# arduino_isp_shield.net
KiCad netlist of a schematic drawn in EAGLE
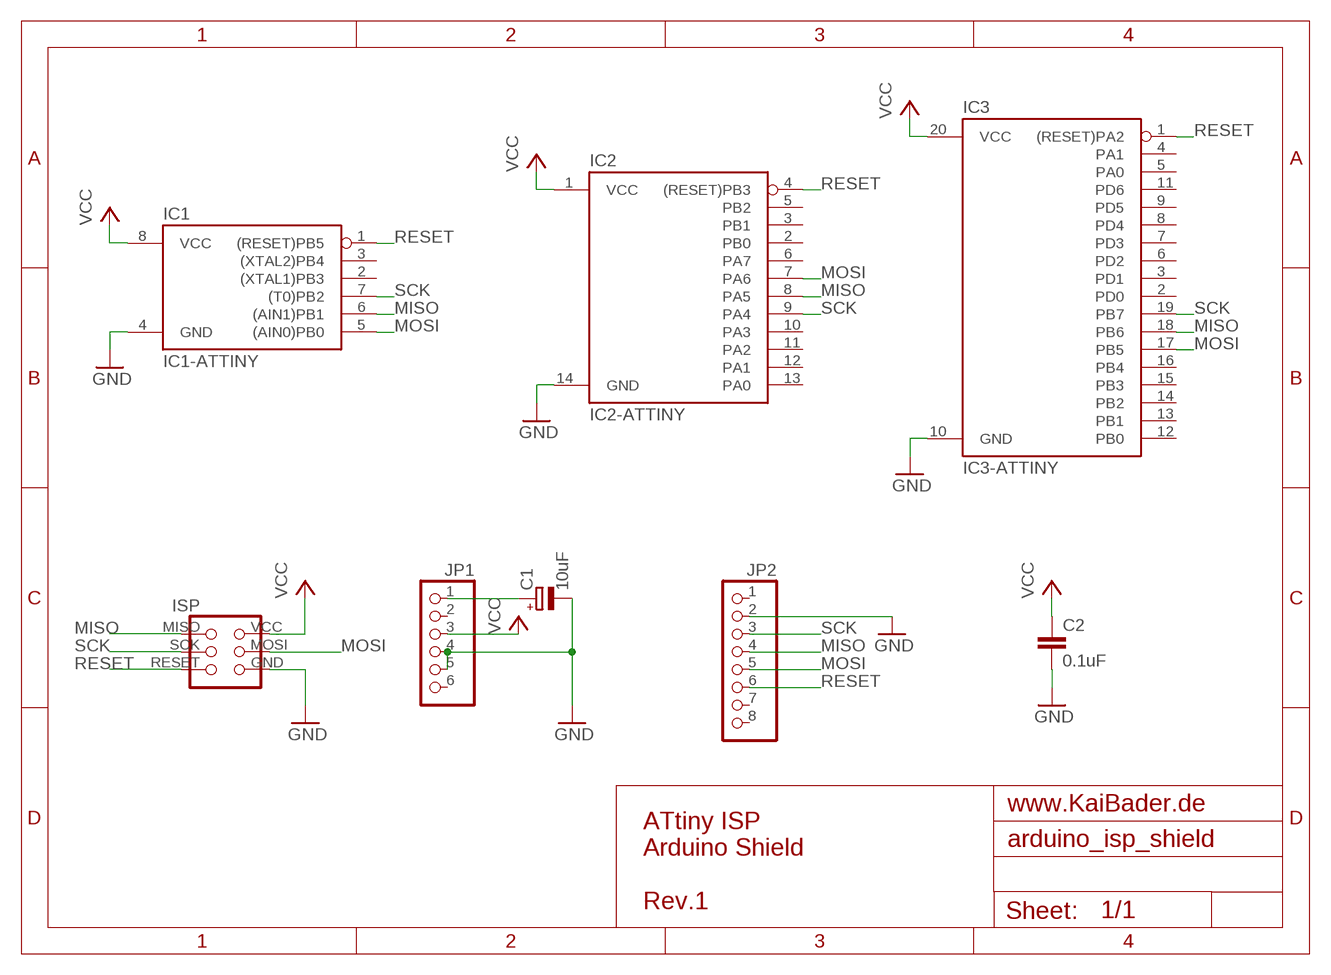
[diagram p0: schematic, sheet 1]

(export (version "E")
  (design (tool "Eeschema 10.0.6"))
  (components
    (comp (ref "C1")
      (value "10uF")
      (footprint "eagle-import:E1,8-4")
      (libsource (lib "eagle-import") (part "CPOL-EUE1.8-4"))
    )
    (comp (ref "C2")
      (value "0.1uF")
      (footprint "eagle-import:C050-025X075")
      (libsource (lib "eagle-import") (part "C-EU050-025X075"))
    )
    (comp (ref "IC1")
      (value "IC1-ATTINY")
      (footprint "eagle-import:DIL08")
      (libsource (lib "eagle-import") (part "TINY85P"))
    )
    (comp (ref "IC2")
      (value "IC2-ATTINY")
      (footprint "eagle-import:DIL14")
      (libsource (lib "eagle-import") (part "TINY84"))
    )
    (comp (ref "IC3")
      (value "IC3-ATTINY")
      (footprint "eagle-import:DIL20")
      (libsource (lib "eagle-import") (part "TINY2313"))
    )
    (comp (ref "ISP")
      (value "AVR-ISP")
      (footprint "eagle-import:AVR-ISP")
      (libsource (lib "eagle-import") (part "AVR-ISP"))
    )
    (comp (ref "JP1")
      (value "PINHD-1X6")
      (footprint "eagle-import:1X06")
      (libsource (lib "eagle-import") (part "PINHD-1X6"))
    )
    (comp (ref "JP2")
      (value "PINHD-1X8")
      (footprint "eagle-import:1X08")
      (libsource (lib "eagle-import") (part "PINHD-1X8"))
    )
  )
  (nets
    (net (code "1") (name "/MISO") (class "Default")
      (node (ref "IC1") (pin "6") (pinfunction "(AIN1)PB1_6") (pintype "bidirectional"))
      (node (ref "IC2") (pin "8") (pinfunction "PA5_8") (pintype "bidirectional"))
      (node (ref "IC3") (pin "18") (pinfunction "PB6_18") (pintype "bidirectional"))
      (node (ref "ISP") (pin "MISO") (pinfunction "MISO_MISO") (pintype "bidirectional"))
      (node (ref "JP2") (pin "4") (pinfunction "4_4") (pintype "passive"))
    )
    (net (code "2") (name "/MOSI") (class "Default")
      (node (ref "IC1") (pin "5") (pinfunction "(AIN0)PB0_5") (pintype "bidirectional"))
      (node (ref "IC2") (pin "7") (pinfunction "PA6_7") (pintype "bidirectional"))
      (node (ref "IC3") (pin "17") (pinfunction "PB5_17") (pintype "bidirectional"))
      (node (ref "ISP") (pin "MOSI") (pinfunction "MOSI_MOSI") (pintype "bidirectional"))
      (node (ref "JP2") (pin "5") (pinfunction "5_5") (pintype "passive"))
    )
    (net (code "3") (name "/RESET") (class "Default")
      (node (ref "IC1") (pin "1") (pinfunction "(RESET)PB5_1") (pintype "bidirectional"))
      (node (ref "IC2") (pin "4") (pinfunction "(RESET)PB3_4") (pintype "bidirectional"))
      (node (ref "IC3") (pin "1") (pinfunction "(RESET)PA2_1") (pintype "bidirectional"))
      (node (ref "ISP") (pin "RESET") (pinfunction "RESET_RESET") (pintype "bidirectional"))
      (node (ref "JP2") (pin "6") (pinfunction "6_6") (pintype "passive"))
    )
    (net (code "4") (name "/SCK") (class "Default")
      (node (ref "IC1") (pin "7") (pinfunction "(T0)PB2_7") (pintype "bidirectional"))
      (node (ref "IC2") (pin "9") (pinfunction "PA4_9") (pintype "bidirectional"))
      (node (ref "IC3") (pin "19") (pinfunction "PB7_19") (pintype "bidirectional"))
      (node (ref "ISP") (pin "SCK") (pinfunction "SCK_SCK") (pintype "bidirectional"))
      (node (ref "JP2") (pin "3") (pinfunction "3_3") (pintype "passive"))
    )
    (net (code "5") (name "GND") (class "Default")
      (node (ref "C1") (pin "-") (pinfunction "-_-") (pintype "passive"))
      (node (ref "C2") (pin "2") (pinfunction "2_2") (pintype "passive"))
      (node (ref "IC1") (pin "4") (pinfunction "GND_4") (pintype "power_in"))
      (node (ref "IC2") (pin "14") (pinfunction "GND_14") (pintype "power_in"))
      (node (ref "IC3") (pin "10") (pinfunction "GND_10") (pintype "power_in"))
      (node (ref "ISP") (pin "GND") (pinfunction "GND_GND") (pintype "power_in"))
      (node (ref "JP1") (pin "4") (pinfunction "4_4") (pintype "passive"))
      (node (ref "JP1") (pin "5") (pinfunction "5_5") (pintype "passive"))
      (node (ref "JP2") (pin "2") (pinfunction "2_2") (pintype "passive"))
    )
    (net (code "6") (name "Net-(C1-Pad+)") (class "Default")
      (node (ref "C1") (pin "+") (pinfunction "+_+") (pintype "passive"))
      (node (ref "JP1") (pin "1") (pinfunction "1_1") (pintype "passive"))
    )
    (net (code "7") (name "VCC") (class "Default")
      (node (ref "C2") (pin "1") (pinfunction "1_1") (pintype "passive"))
      (node (ref "IC1") (pin "8") (pinfunction "VCC_8") (pintype "power_in"))
      (node (ref "IC2") (pin "1") (pinfunction "VCC_1") (pintype "power_in"))
      (node (ref "IC3") (pin "20") (pinfunction "VCC_20") (pintype "power_in"))
      (node (ref "ISP") (pin "VCC") (pinfunction "VCC_VCC") (pintype "power_in"))
      (node (ref "JP1") (pin "3") (pinfunction "3_3") (pintype "passive"))
    )
    (net (code "8") (name "unconnected-(IC1-(XTAL1)PB3-Pad2)") (class "Default")
      (node (ref "IC1") (pin "2") (pinfunction "(XTAL1)PB3_2") (pintype "bidirectional"))
    )
    (net (code "9") (name "unconnected-(IC1-(XTAL2)PB4-Pad3)") (class "Default")
      (node (ref "IC1") (pin "3") (pinfunction "(XTAL2)PB4_3") (pintype "bidirectional"))
    )
    (net (code "10") (name "unconnected-(IC2-PA0-Pad13)") (class "Default")
      (node (ref "IC2") (pin "13") (pinfunction "PA0_13") (pintype "bidirectional"))
    )
    (net (code "11") (name "unconnected-(IC2-PA1-Pad12)") (class "Default")
      (node (ref "IC2") (pin "12") (pinfunction "PA1_12") (pintype "bidirectional"))
    )
    (net (code "12") (name "unconnected-(IC2-PA2-Pad11)") (class "Default")
      (node (ref "IC2") (pin "11") (pinfunction "PA2_11") (pintype "bidirectional"))
    )
    (net (code "13") (name "unconnected-(IC2-PA3-Pad10)") (class "Default")
      (node (ref "IC2") (pin "10") (pinfunction "PA3_10") (pintype "bidirectional"))
    )
    (net (code "14") (name "unconnected-(IC2-PA7-Pad6)") (class "Default")
      (node (ref "IC2") (pin "6") (pinfunction "PA7_6") (pintype "bidirectional"))
    )
    (net (code "15") (name "unconnected-(IC2-PB0-Pad2)") (class "Default")
      (node (ref "IC2") (pin "2") (pinfunction "PB0_2") (pintype "bidirectional"))
    )
    (net (code "16") (name "unconnected-(IC2-PB1-Pad3)") (class "Default")
      (node (ref "IC2") (pin "3") (pinfunction "PB1_3") (pintype "bidirectional"))
    )
    (net (code "17") (name "unconnected-(IC2-PB2-Pad5)") (class "Default")
      (node (ref "IC2") (pin "5") (pinfunction "PB2_5") (pintype "bidirectional"))
    )
    (net (code "18") (name "unconnected-(IC3-PA0-Pad5)") (class "Default")
      (node (ref "IC3") (pin "5") (pinfunction "PA0_5") (pintype "bidirectional"))
    )
    (net (code "19") (name "unconnected-(IC3-PA1-Pad4)") (class "Default")
      (node (ref "IC3") (pin "4") (pinfunction "PA1_4") (pintype "bidirectional"))
    )
    (net (code "20") (name "unconnected-(IC3-PB0-Pad12)") (class "Default")
      (node (ref "IC3") (pin "12") (pinfunction "PB0_12") (pintype "bidirectional"))
    )
    (net (code "21") (name "unconnected-(IC3-PB1-Pad13)") (class "Default")
      (node (ref "IC3") (pin "13") (pinfunction "PB1_13") (pintype "bidirectional"))
    )
    (net (code "22") (name "unconnected-(IC3-PB2-Pad14)") (class "Default")
      (node (ref "IC3") (pin "14") (pinfunction "PB2_14") (pintype "bidirectional"))
    )
    (net (code "23") (name "unconnected-(IC3-PB3-Pad15)") (class "Default")
      (node (ref "IC3") (pin "15") (pinfunction "PB3_15") (pintype "bidirectional"))
    )
    (net (code "24") (name "unconnected-(IC3-PB4-Pad16)") (class "Default")
      (node (ref "IC3") (pin "16") (pinfunction "PB4_16") (pintype "bidirectional"))
    )
    (net (code "25") (name "unconnected-(IC3-PD0-Pad2)") (class "Default")
      (node (ref "IC3") (pin "2") (pinfunction "PD0_2") (pintype "bidirectional"))
    )
    (net (code "26") (name "unconnected-(IC3-PD1-Pad3)") (class "Default")
      (node (ref "IC3") (pin "3") (pinfunction "PD1_3") (pintype "bidirectional"))
    )
    (net (code "27") (name "unconnected-(IC3-PD2-Pad6)") (class "Default")
      (node (ref "IC3") (pin "6") (pinfunction "PD2_6") (pintype "bidirectional"))
    )
    (net (code "28") (name "unconnected-(IC3-PD3-Pad7)") (class "Default")
      (node (ref "IC3") (pin "7") (pinfunction "PD3_7") (pintype "bidirectional"))
    )
    (net (code "29") (name "unconnected-(IC3-PD4-Pad8)") (class "Default")
      (node (ref "IC3") (pin "8") (pinfunction "PD4_8") (pintype "bidirectional"))
    )
    (net (code "30") (name "unconnected-(IC3-PD5-Pad9)") (class "Default")
      (node (ref "IC3") (pin "9") (pinfunction "PD5_9") (pintype "bidirectional"))
    )
    (net (code "31") (name "unconnected-(IC3-PD6-Pad11)") (class "Default")
      (node (ref "IC3") (pin "11") (pinfunction "PD6_11") (pintype "bidirectional"))
    )
    (net (code "32") (name "unconnected-(JP1-Pad2)") (class "Default")
      (node (ref "JP1") (pin "2") (pinfunction "2_2") (pintype "passive"))
    )
    (net (code "33") (name "unconnected-(JP1-Pad6)") (class "Default")
      (node (ref "JP1") (pin "6") (pinfunction "6_6") (pintype "passive"))
    )
    (net (code "34") (name "unconnected-(JP2-Pad1)") (class "Default")
      (node (ref "JP2") (pin "1") (pinfunction "1_1") (pintype "passive"))
    )
    (net (code "35") (name "unconnected-(JP2-Pad7)") (class "Default")
      (node (ref "JP2") (pin "7") (pinfunction "7_7") (pintype "passive"))
    )
    (net (code "36") (name "unconnected-(JP2-Pad8)") (class "Default")
      (node (ref "JP2") (pin "8") (pinfunction "8_8") (pintype "passive"))
    )
  )
)
